# SCH_d_00_e_01.net
KiCad netlist of a schematic drawn in EasyEDA
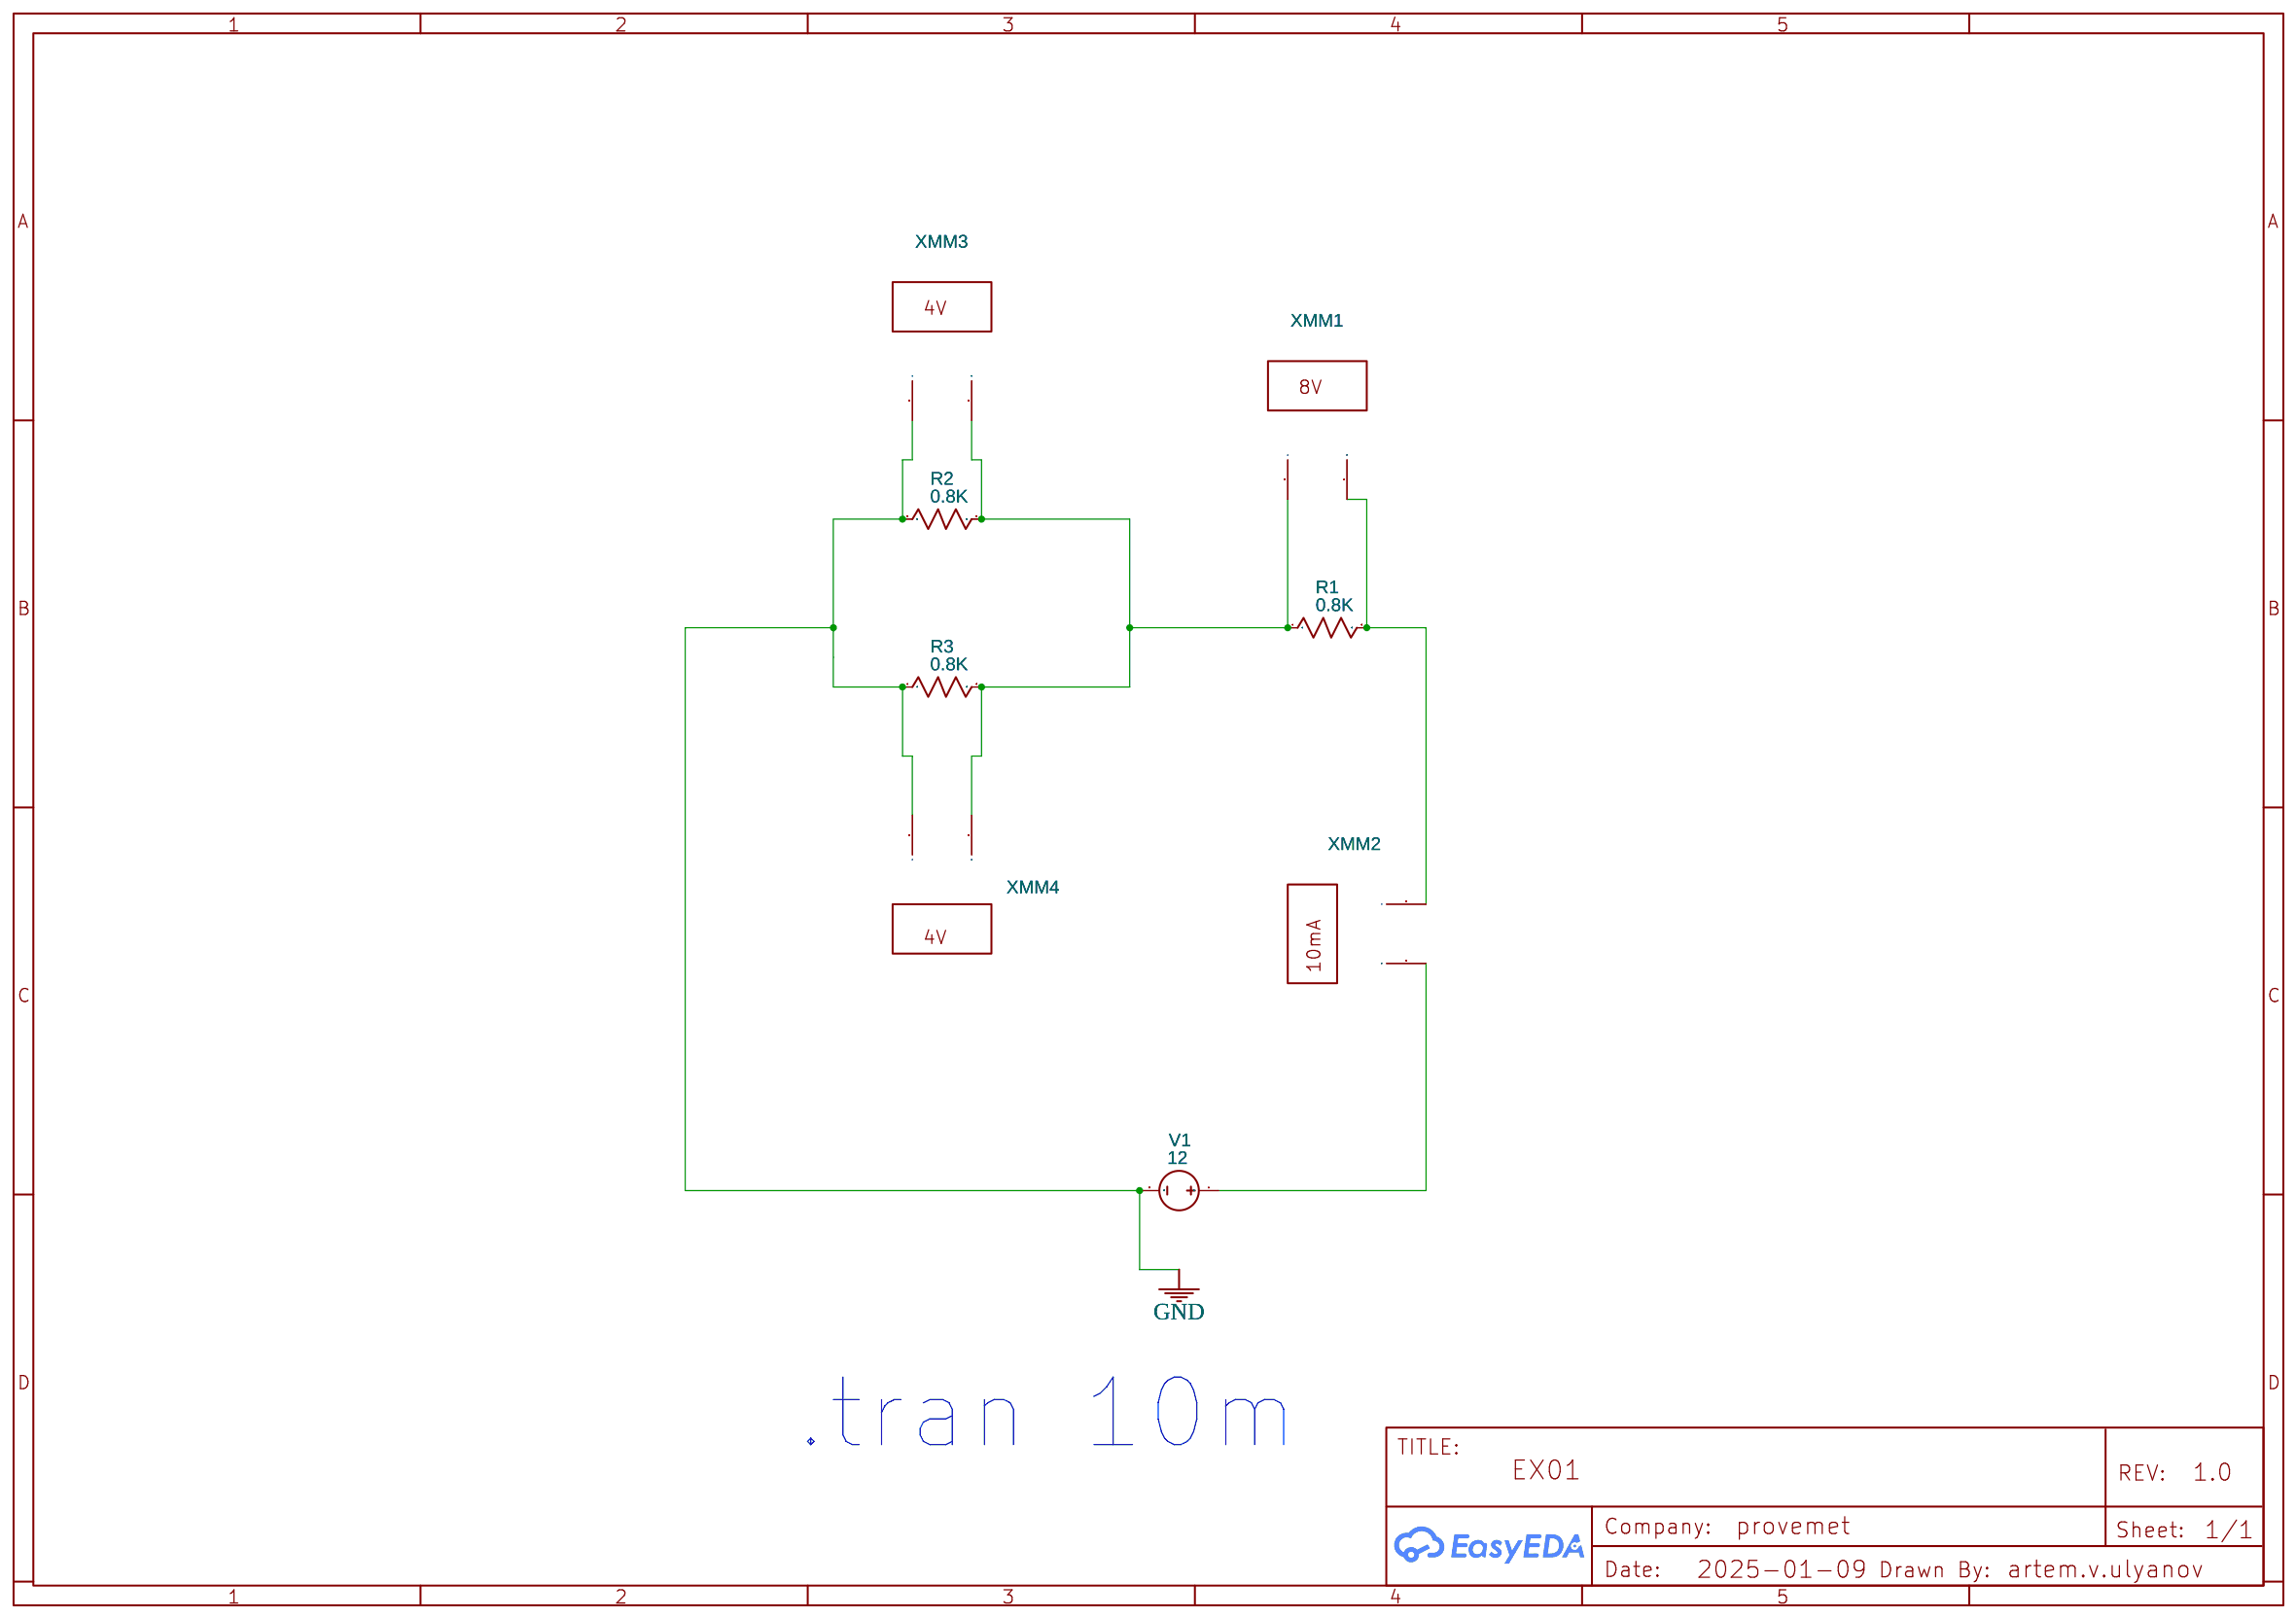
[diagram p0: schematic sheet]

(export (version "E")
  (design (tool "Eeschema 10.0.6"))
  (components
    (comp (ref "R1") (value "0.8K") (libsource (lib "") (part "Resistor_US")))
    (comp (ref "R2") (value "0.8K") (libsource (lib "") (part "Resistor_US")))
    (comp (ref "R3") (value "0.8K") (libsource (lib "") (part "Resistor_US")))
    (comp (ref "V1") (value "12") (libsource (lib "") (part "VDC")))
    (comp (ref "XMM1") (value "Multimeter") (libsource (lib "") (part "MULTIMETER_1")))
    (comp (ref "XMM2") (value "Multimeter") (libsource (lib "") (part "MULTIMETER_3")))
    (comp (ref "XMM3") (value "Multimeter") (libsource (lib "") (part "MULTIMETER_2")))
    (comp (ref "XMM4") (value "Multimeter") (libsource (lib "") (part "MULTIMETER")))
  )
  (nets
    (net (code "1") (name "GND") (class "Default")
      (node (ref "R2") (pin "1") (pinfunction "1_1") (pintype "unspecified"))
      (node (ref "R3") (pin "1") (pinfunction "1_1") (pintype "unspecified"))
      (node (ref "V1") (pin "2") (pinfunction "2_2") (pintype "unspecified"))
      (node (ref "XMM3") (pin "2") (pinfunction "I_2") (pintype "unspecified"))
      (node (ref "XMM4") (pin "2") (pinfunction "I_2") (pintype "unspecified"))
    )
    (net (code "2") (name "Net-(XMM1-+)") (class "Default")
      (node (ref "R1") (pin "2") (pinfunction "2_2") (pintype "unspecified"))
      (node (ref "XMM1") (pin "1") (pinfunction "+_1") (pintype "unspecified"))
      (node (ref "XMM2") (pin "2") (pinfunction "I_2") (pintype "unspecified"))
    )
    (net (code "3") (name "Net-(XMM1-I)") (class "Default")
      (node (ref "R1") (pin "1") (pinfunction "1_1") (pintype "unspecified"))
      (node (ref "R2") (pin "2") (pinfunction "2_2") (pintype "unspecified"))
      (node (ref "R3") (pin "2") (pinfunction "2_2") (pintype "unspecified"))
      (node (ref "XMM1") (pin "2") (pinfunction "I_2") (pintype "unspecified"))
      (node (ref "XMM3") (pin "1") (pinfunction "+_1") (pintype "unspecified"))
      (node (ref "XMM4") (pin "1") (pinfunction "+_1") (pintype "unspecified"))
    )
    (net (code "4") (name "Net-(XMM2-+)") (class "Default")
      (node (ref "V1") (pin "1") (pinfunction "1_1") (pintype "unspecified"))
      (node (ref "XMM2") (pin "1") (pinfunction "+_1") (pintype "unspecified"))
    )
  )
)
